# Sensor_Bar_2_0_signal_LED.net
KiCad netlist of a schematic drawn in Altium Designer
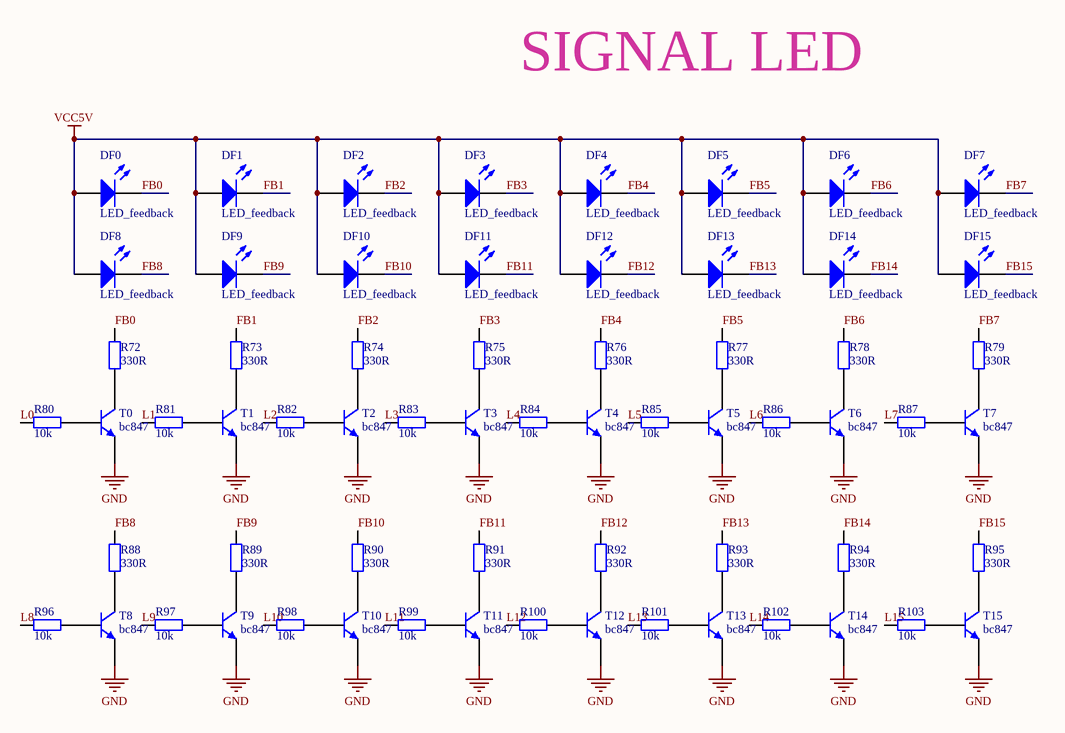
[diagram p0: Sensor Bar 2.0 signal LED.SchDoc]

(export (version "E")
  (design (tool "Eeschema 10.0.6"))
  (components
    (comp (ref "DF0")
      (value "LED_feedback")
      (footprint "SMD _LED")
      (description "Typical RED GaAs LED")
      (fields (field (name "PUBLISHER") "Altium Limited"))
      (libsource (lib "Robocon_BJT") (part "LED"))
    )
    (comp (ref "DF1")
      (value "LED_feedback")
      (footprint "SMD _LED")
      (description "Typical RED GaAs LED")
      (fields (field (name "PUBLISHER") "Altium Limited"))
      (libsource (lib "Robocon_BJT") (part "LED"))
    )
    (comp (ref "DF2")
      (value "LED_feedback")
      (footprint "SMD _LED")
      (description "Typical RED GaAs LED")
      (fields (field (name "PUBLISHER") "Altium Limited"))
      (libsource (lib "Robocon_BJT") (part "LED"))
    )
    (comp (ref "DF3")
      (value "LED_feedback")
      (footprint "SMD _LED")
      (description "Typical RED GaAs LED")
      (fields (field (name "PUBLISHER") "Altium Limited"))
      (libsource (lib "Robocon_BJT") (part "LED"))
    )
    (comp (ref "DF4")
      (value "LED_feedback")
      (footprint "SMD _LED")
      (description "Typical RED GaAs LED")
      (fields (field (name "PUBLISHER") "Altium Limited"))
      (libsource (lib "Robocon_BJT") (part "LED"))
    )
    (comp (ref "DF5")
      (value "LED_feedback")
      (footprint "SMD _LED")
      (description "Typical RED GaAs LED")
      (fields (field (name "PUBLISHER") "Altium Limited"))
      (libsource (lib "Robocon_BJT") (part "LED"))
    )
    (comp (ref "DF6")
      (value "LED_feedback")
      (footprint "SMD _LED")
      (description "Typical RED GaAs LED")
      (fields (field (name "PUBLISHER") "Altium Limited"))
      (libsource (lib "Robocon_BJT") (part "LED"))
    )
    (comp (ref "DF7")
      (value "LED_feedback")
      (footprint "SMD _LED")
      (description "Typical RED GaAs LED")
      (fields (field (name "PUBLISHER") "Altium Limited"))
      (libsource (lib "Robocon_BJT") (part "LED"))
    )
    (comp (ref "DF8")
      (value "LED_feedback")
      (footprint "SMD _LED")
      (description "Typical RED GaAs LED")
      (fields (field (name "PUBLISHER") "Altium Limited"))
      (libsource (lib "Robocon_BJT") (part "LED"))
    )
    (comp (ref "DF9")
      (value "LED_feedback")
      (footprint "SMD _LED")
      (description "Typical RED GaAs LED")
      (fields (field (name "PUBLISHER") "Altium Limited"))
      (libsource (lib "Robocon_BJT") (part "LED"))
    )
    (comp (ref "DF10")
      (value "LED_feedback")
      (footprint "SMD _LED")
      (description "Typical RED GaAs LED")
      (fields (field (name "PUBLISHER") "Altium Limited"))
      (libsource (lib "Robocon_BJT") (part "LED"))
    )
    (comp (ref "DF11")
      (value "LED_feedback")
      (footprint "SMD _LED")
      (description "Typical RED GaAs LED")
      (fields (field (name "PUBLISHER") "Altium Limited"))
      (libsource (lib "Robocon_BJT") (part "LED"))
    )
    (comp (ref "DF12")
      (value "LED_feedback")
      (footprint "SMD _LED")
      (description "Typical RED GaAs LED")
      (fields (field (name "PUBLISHER") "Altium Limited"))
      (libsource (lib "Robocon_BJT") (part "LED"))
    )
    (comp (ref "DF13")
      (value "LED_feedback")
      (footprint "SMD _LED")
      (description "Typical RED GaAs LED")
      (fields (field (name "PUBLISHER") "Altium Limited"))
      (libsource (lib "Robocon_BJT") (part "LED"))
    )
    (comp (ref "DF14")
      (value "LED_feedback")
      (footprint "SMD _LED")
      (description "Typical RED GaAs LED")
      (fields (field (name "PUBLISHER") "Altium Limited"))
      (libsource (lib "Robocon_BJT") (part "LED"))
    )
    (comp (ref "DF15")
      (value "LED_feedback")
      (footprint "SMD _LED")
      (description "Typical RED GaAs LED")
      (fields (field (name "PUBLISHER") "Altium Limited"))
      (libsource (lib "Robocon_BJT") (part "LED"))
    )
    (comp (ref "R72")
      (value "330R")
      (footprint "CR2012-0805")
      (description "Resistor")
      (fields (field (name "PUBLISHER") "Altium Limited"))
      (libsource (lib "Robocon_RCL") (part "Res2"))
    )
    (comp (ref "R73")
      (value "330R")
      (footprint "CR2012-0805")
      (description "Resistor")
      (fields (field (name "PUBLISHER") "Altium Limited"))
      (libsource (lib "Robocon_RCL") (part "Res2"))
    )
    (comp (ref "R74")
      (value "330R")
      (footprint "CR2012-0805")
      (description "Resistor")
      (fields (field (name "PUBLISHER") "Altium Limited"))
      (libsource (lib "Robocon_RCL") (part "Res2"))
    )
    (comp (ref "R75")
      (value "330R")
      (footprint "CR2012-0805")
      (description "Resistor")
      (fields (field (name "PUBLISHER") "Altium Limited"))
      (libsource (lib "Robocon_RCL") (part "Res2"))
    )
    (comp (ref "R76")
      (value "330R")
      (footprint "CR2012-0805")
      (description "Resistor")
      (fields (field (name "PUBLISHER") "Altium Limited"))
      (libsource (lib "Robocon_RCL") (part "Res2"))
    )
    (comp (ref "R77")
      (value "330R")
      (footprint "CR2012-0805")
      (description "Resistor")
      (fields (field (name "PUBLISHER") "Altium Limited"))
      (libsource (lib "Robocon_RCL") (part "Res2"))
    )
    (comp (ref "R78")
      (value "330R")
      (footprint "CR2012-0805")
      (description "Resistor")
      (fields (field (name "PUBLISHER") "Altium Limited"))
      (libsource (lib "Robocon_RCL") (part "Res2"))
    )
    (comp (ref "R79")
      (value "330R")
      (footprint "CR2012-0805")
      (description "Resistor")
      (fields (field (name "PUBLISHER") "Altium Limited"))
      (libsource (lib "Robocon_RCL") (part "Res2"))
    )
    (comp (ref "R80")
      (value "10k")
      (footprint "CR2012-0805")
      (description "Resistor")
      (fields (field (name "PUBLISHER") "Altium Limited"))
      (libsource (lib "") (part "Res2_1"))
    )
    (comp (ref "R81")
      (value "10k")
      (footprint "CR2012-0805")
      (description "Resistor")
      (fields (field (name "PUBLISHER") "Altium Limited"))
      (libsource (lib "") (part "Res2_1"))
    )
    (comp (ref "R82")
      (value "10k")
      (footprint "CR2012-0805")
      (description "Resistor")
      (fields (field (name "PUBLISHER") "Altium Limited"))
      (libsource (lib "") (part "Res2_1"))
    )
    (comp (ref "R83")
      (value "10k")
      (footprint "CR2012-0805")
      (description "Resistor")
      (fields (field (name "PUBLISHER") "Altium Limited"))
      (libsource (lib "") (part "Res2_1"))
    )
    (comp (ref "R84")
      (value "10k")
      (footprint "CR2012-0805")
      (description "Resistor")
      (fields (field (name "PUBLISHER") "Altium Limited"))
      (libsource (lib "") (part "Res2_1"))
    )
    (comp (ref "R85")
      (value "10k")
      (footprint "CR2012-0805")
      (description "Resistor")
      (fields (field (name "PUBLISHER") "Altium Limited"))
      (libsource (lib "") (part "Res2_1"))
    )
    (comp (ref "R86")
      (value "10k")
      (footprint "CR2012-0805")
      (description "Resistor")
      (fields (field (name "PUBLISHER") "Altium Limited"))
      (libsource (lib "") (part "Res2_1"))
    )
    (comp (ref "R87")
      (value "10k")
      (footprint "CR2012-0805")
      (description "Resistor")
      (fields (field (name "PUBLISHER") "Altium Limited"))
      (libsource (lib "") (part "Res2_1"))
    )
    (comp (ref "R88")
      (value "330R")
      (footprint "CR2012-0805")
      (description "Resistor")
      (fields (field (name "PUBLISHER") "Altium Limited"))
      (libsource (lib "Robocon_RCL") (part "Res2"))
    )
    (comp (ref "R89")
      (value "330R")
      (footprint "CR2012-0805")
      (description "Resistor")
      (fields (field (name "PUBLISHER") "Altium Limited"))
      (libsource (lib "Robocon_RCL") (part "Res2"))
    )
    (comp (ref "R90")
      (value "330R")
      (footprint "CR2012-0805")
      (description "Resistor")
      (fields (field (name "PUBLISHER") "Altium Limited"))
      (libsource (lib "Robocon_RCL") (part "Res2"))
    )
    (comp (ref "R91")
      (value "330R")
      (footprint "CR2012-0805")
      (description "Resistor")
      (fields (field (name "PUBLISHER") "Altium Limited"))
      (libsource (lib "Robocon_RCL") (part "Res2"))
    )
    (comp (ref "R92")
      (value "330R")
      (footprint "CR2012-0805")
      (description "Resistor")
      (fields (field (name "PUBLISHER") "Altium Limited"))
      (libsource (lib "Robocon_RCL") (part "Res2"))
    )
    (comp (ref "R93")
      (value "330R")
      (footprint "CR2012-0805")
      (description "Resistor")
      (fields (field (name "PUBLISHER") "Altium Limited"))
      (libsource (lib "Robocon_RCL") (part "Res2"))
    )
    (comp (ref "R94")
      (value "330R")
      (footprint "CR2012-0805")
      (description "Resistor")
      (fields (field (name "PUBLISHER") "Altium Limited"))
      (libsource (lib "Robocon_RCL") (part "Res2"))
    )
    (comp (ref "R95")
      (value "330R")
      (footprint "CR2012-0805")
      (description "Resistor")
      (fields (field (name "PUBLISHER") "Altium Limited"))
      (libsource (lib "Robocon_RCL") (part "Res2"))
    )
    (comp (ref "R96")
      (value "10k")
      (footprint "CR2012-0805")
      (description "Resistor")
      (fields (field (name "PUBLISHER") "Altium Limited"))
      (libsource (lib "") (part "Res2_1"))
    )
    (comp (ref "R97")
      (value "10k")
      (footprint "CR2012-0805")
      (description "Resistor")
      (fields (field (name "PUBLISHER") "Altium Limited"))
      (libsource (lib "") (part "Res2_1"))
    )
    (comp (ref "R98")
      (value "10k")
      (footprint "CR2012-0805")
      (description "Resistor")
      (fields (field (name "PUBLISHER") "Altium Limited"))
      (libsource (lib "") (part "Res2_1"))
    )
    (comp (ref "R99")
      (value "10k")
      (footprint "CR2012-0805")
      (description "Resistor")
      (fields (field (name "PUBLISHER") "Altium Limited"))
      (libsource (lib "") (part "Res2_1"))
    )
    (comp (ref "R100")
      (value "10k")
      (footprint "CR2012-0805")
      (description "Resistor")
      (fields (field (name "PUBLISHER") "Altium Limited"))
      (libsource (lib "") (part "Res2_1"))
    )
    (comp (ref "R101")
      (value "10k")
      (footprint "CR2012-0805")
      (description "Resistor")
      (fields (field (name "PUBLISHER") "Altium Limited"))
      (libsource (lib "") (part "Res2_1"))
    )
    (comp (ref "R102")
      (value "10k")
      (footprint "CR2012-0805")
      (description "Resistor")
      (fields (field (name "PUBLISHER") "Altium Limited"))
      (libsource (lib "") (part "Res2_1"))
    )
    (comp (ref "R103")
      (value "10k")
      (footprint "CR2012-0805")
      (description "Resistor")
      (fields (field (name "PUBLISHER") "Altium Limited"))
      (libsource (lib "") (part "Res2_1"))
    )
    (comp (ref "T0") (value "bc847") (footprint "npn") (libsource (lib "三极管") (part "npn")))
    (comp (ref "T1") (value "bc847") (footprint "npn") (libsource (lib "三极管") (part "npn")))
    (comp (ref "T2") (value "bc847") (footprint "npn") (libsource (lib "三极管") (part "npn")))
    (comp (ref "T3") (value "bc847") (footprint "npn") (libsource (lib "三极管") (part "npn")))
    (comp (ref "T4") (value "bc847") (footprint "npn") (libsource (lib "三极管") (part "npn")))
    (comp (ref "T5") (value "bc847") (footprint "npn") (libsource (lib "三极管") (part "npn")))
    (comp (ref "T6") (value "bc847") (footprint "npn") (libsource (lib "三极管") (part "npn")))
    (comp (ref "T7") (value "bc847") (footprint "npn") (libsource (lib "三极管") (part "npn")))
    (comp (ref "T8") (value "bc847") (footprint "npn") (libsource (lib "三极管") (part "npn")))
    (comp (ref "T9") (value "bc847") (footprint "npn") (libsource (lib "三极管") (part "npn")))
    (comp (ref "T10") (value "bc847") (footprint "npn") (libsource (lib "三极管") (part "npn")))
    (comp (ref "T11") (value "bc847") (footprint "npn") (libsource (lib "三极管") (part "npn")))
    (comp (ref "T12") (value "bc847") (footprint "npn") (libsource (lib "三极管") (part "npn")))
    (comp (ref "T13") (value "bc847") (footprint "npn") (libsource (lib "三极管") (part "npn")))
    (comp (ref "T14") (value "bc847") (footprint "npn") (libsource (lib "三极管") (part "npn")))
    (comp (ref "T15") (value "bc847") (footprint "npn") (libsource (lib "三极管") (part "npn")))
  )
  (nets
    (net (code "1") (name "/FB0") (class "Default")
      (node (ref "DF0") (pin "2") (pinfunction "K_2") (pintype "passive"))
      (node (ref "R72") (pin "2") (pinfunction "2_2") (pintype "passive"))
    )
    (net (code "2") (name "/FB1") (class "Default")
      (node (ref "DF1") (pin "2") (pinfunction "K_2") (pintype "passive"))
      (node (ref "R73") (pin "2") (pinfunction "2_2") (pintype "passive"))
    )
    (net (code "3") (name "/FB2") (class "Default")
      (node (ref "DF2") (pin "2") (pinfunction "K_2") (pintype "passive"))
      (node (ref "R74") (pin "2") (pinfunction "2_2") (pintype "passive"))
    )
    (net (code "4") (name "/FB3") (class "Default")
      (node (ref "DF3") (pin "2") (pinfunction "K_2") (pintype "passive"))
      (node (ref "R75") (pin "2") (pinfunction "2_2") (pintype "passive"))
    )
    (net (code "5") (name "/FB4") (class "Default")
      (node (ref "DF4") (pin "2") (pinfunction "K_2") (pintype "passive"))
      (node (ref "R76") (pin "2") (pinfunction "2_2") (pintype "passive"))
    )
    (net (code "6") (name "/FB5") (class "Default")
      (node (ref "DF5") (pin "2") (pinfunction "K_2") (pintype "passive"))
      (node (ref "R77") (pin "2") (pinfunction "2_2") (pintype "passive"))
    )
    (net (code "7") (name "/FB6") (class "Default")
      (node (ref "DF6") (pin "2") (pinfunction "K_2") (pintype "passive"))
      (node (ref "R78") (pin "2") (pinfunction "2_2") (pintype "passive"))
    )
    (net (code "8") (name "/FB7") (class "Default")
      (node (ref "DF7") (pin "2") (pinfunction "K_2") (pintype "passive"))
      (node (ref "R79") (pin "2") (pinfunction "2_2") (pintype "passive"))
    )
    (net (code "9") (name "/FB8") (class "Default")
      (node (ref "DF8") (pin "2") (pinfunction "K_2") (pintype "passive"))
      (node (ref "R88") (pin "2") (pinfunction "2_2") (pintype "passive"))
    )
    (net (code "10") (name "/FB9") (class "Default")
      (node (ref "DF9") (pin "2") (pinfunction "K_2") (pintype "passive"))
      (node (ref "R89") (pin "2") (pinfunction "2_2") (pintype "passive"))
    )
    (net (code "11") (name "/FB10") (class "Default")
      (node (ref "DF10") (pin "2") (pinfunction "K_2") (pintype "passive"))
      (node (ref "R90") (pin "2") (pinfunction "2_2") (pintype "passive"))
    )
    (net (code "12") (name "/FB11") (class "Default")
      (node (ref "DF11") (pin "2") (pinfunction "K_2") (pintype "passive"))
      (node (ref "R91") (pin "2") (pinfunction "2_2") (pintype "passive"))
    )
    (net (code "13") (name "/FB12") (class "Default")
      (node (ref "DF12") (pin "2") (pinfunction "K_2") (pintype "passive"))
      (node (ref "R92") (pin "2") (pinfunction "2_2") (pintype "passive"))
    )
    (net (code "14") (name "/FB13") (class "Default")
      (node (ref "DF13") (pin "2") (pinfunction "K_2") (pintype "passive"))
      (node (ref "R93") (pin "2") (pinfunction "2_2") (pintype "passive"))
    )
    (net (code "15") (name "/FB14") (class "Default")
      (node (ref "DF14") (pin "2") (pinfunction "K_2") (pintype "passive"))
      (node (ref "R94") (pin "2") (pinfunction "2_2") (pintype "passive"))
    )
    (net (code "16") (name "/FB15") (class "Default")
      (node (ref "DF15") (pin "2") (pinfunction "K_2") (pintype "passive"))
      (node (ref "R95") (pin "2") (pinfunction "2_2") (pintype "passive"))
    )
    (net (code "17") (name "/L0") (class "Default")
      (node (ref "R80") (pin "2") (pinfunction "2_2") (pintype "passive"))
    )
    (net (code "18") (name "/L1") (class "Default")
      (node (ref "R81") (pin "2") (pinfunction "2_2") (pintype "passive"))
    )
    (net (code "19") (name "/L2") (class "Default")
      (node (ref "R82") (pin "2") (pinfunction "2_2") (pintype "passive"))
    )
    (net (code "20") (name "/L3") (class "Default")
      (node (ref "R83") (pin "2") (pinfunction "2_2") (pintype "passive"))
    )
    (net (code "21") (name "/L4") (class "Default")
      (node (ref "R84") (pin "2") (pinfunction "2_2") (pintype "passive"))
    )
    (net (code "22") (name "/L5") (class "Default")
      (node (ref "R85") (pin "2") (pinfunction "2_2") (pintype "passive"))
    )
    (net (code "23") (name "/L6") (class "Default")
      (node (ref "R86") (pin "2") (pinfunction "2_2") (pintype "passive"))
    )
    (net (code "24") (name "/L7") (class "Default")
      (node (ref "R87") (pin "2") (pinfunction "2_2") (pintype "passive"))
    )
    (net (code "25") (name "/L8") (class "Default")
      (node (ref "R96") (pin "2") (pinfunction "2_2") (pintype "passive"))
    )
    (net (code "26") (name "/L9") (class "Default")
      (node (ref "R97") (pin "2") (pinfunction "2_2") (pintype "passive"))
    )
    (net (code "27") (name "/L10") (class "Default")
      (node (ref "R98") (pin "2") (pinfunction "2_2") (pintype "passive"))
    )
    (net (code "28") (name "/L11") (class "Default")
      (node (ref "R99") (pin "2") (pinfunction "2_2") (pintype "passive"))
    )
    (net (code "29") (name "/L12") (class "Default")
      (node (ref "R100") (pin "2") (pinfunction "2_2") (pintype "passive"))
    )
    (net (code "30") (name "/L13") (class "Default")
      (node (ref "R101") (pin "2") (pinfunction "2_2") (pintype "passive"))
    )
    (net (code "31") (name "/L14") (class "Default")
      (node (ref "R102") (pin "2") (pinfunction "2_2") (pintype "passive"))
    )
    (net (code "32") (name "/L15") (class "Default")
      (node (ref "R103") (pin "2") (pinfunction "2_2") (pintype "passive"))
    )
    (net (code "33") (name "GND") (class "Default")
      (node (ref "T0") (pin "2") (pinfunction "E_2") (pintype "passive"))
      (node (ref "T1") (pin "2") (pinfunction "E_2") (pintype "passive"))
      (node (ref "T10") (pin "2") (pinfunction "E_2") (pintype "passive"))
      (node (ref "T11") (pin "2") (pinfunction "E_2") (pintype "passive"))
      (node (ref "T12") (pin "2") (pinfunction "E_2") (pintype "passive"))
      (node (ref "T13") (pin "2") (pinfunction "E_2") (pintype "passive"))
      (node (ref "T14") (pin "2") (pinfunction "E_2") (pintype "passive"))
      (node (ref "T15") (pin "2") (pinfunction "E_2") (pintype "passive"))
      (node (ref "T2") (pin "2") (pinfunction "E_2") (pintype "passive"))
      (node (ref "T3") (pin "2") (pinfunction "E_2") (pintype "passive"))
      (node (ref "T4") (pin "2") (pinfunction "E_2") (pintype "passive"))
      (node (ref "T5") (pin "2") (pinfunction "E_2") (pintype "passive"))
      (node (ref "T6") (pin "2") (pinfunction "E_2") (pintype "passive"))
      (node (ref "T7") (pin "2") (pinfunction "E_2") (pintype "passive"))
      (node (ref "T8") (pin "2") (pinfunction "E_2") (pintype "passive"))
      (node (ref "T9") (pin "2") (pinfunction "E_2") (pintype "passive"))
    )
    (net (code "34") (name "Net-(T0-B)") (class "Default")
      (node (ref "R80") (pin "1") (pinfunction "1_1") (pintype "passive"))
      (node (ref "T0") (pin "1") (pinfunction "B_1") (pintype "passive"))
    )
    (net (code "35") (name "Net-(T0-C)") (class "Default")
      (node (ref "R72") (pin "1") (pinfunction "1_1") (pintype "passive"))
      (node (ref "T0") (pin "3") (pinfunction "C_3") (pintype "passive"))
    )
    (net (code "36") (name "Net-(T1-B)") (class "Default")
      (node (ref "R81") (pin "1") (pinfunction "1_1") (pintype "passive"))
      (node (ref "T1") (pin "1") (pinfunction "B_1") (pintype "passive"))
    )
    (net (code "37") (name "Net-(T1-C)") (class "Default")
      (node (ref "R73") (pin "1") (pinfunction "1_1") (pintype "passive"))
      (node (ref "T1") (pin "3") (pinfunction "C_3") (pintype "passive"))
    )
    (net (code "38") (name "Net-(T2-B)") (class "Default")
      (node (ref "R82") (pin "1") (pinfunction "1_1") (pintype "passive"))
      (node (ref "T2") (pin "1") (pinfunction "B_1") (pintype "passive"))
    )
    (net (code "39") (name "Net-(T2-C)") (class "Default")
      (node (ref "R74") (pin "1") (pinfunction "1_1") (pintype "passive"))
      (node (ref "T2") (pin "3") (pinfunction "C_3") (pintype "passive"))
    )
    (net (code "40") (name "Net-(T3-B)") (class "Default")
      (node (ref "R83") (pin "1") (pinfunction "1_1") (pintype "passive"))
      (node (ref "T3") (pin "1") (pinfunction "B_1") (pintype "passive"))
    )
    (net (code "41") (name "Net-(T3-C)") (class "Default")
      (node (ref "R75") (pin "1") (pinfunction "1_1") (pintype "passive"))
      (node (ref "T3") (pin "3") (pinfunction "C_3") (pintype "passive"))
    )
    (net (code "42") (name "Net-(T4-B)") (class "Default")
      (node (ref "R84") (pin "1") (pinfunction "1_1") (pintype "passive"))
      (node (ref "T4") (pin "1") (pinfunction "B_1") (pintype "passive"))
    )
    (net (code "43") (name "Net-(T4-C)") (class "Default")
      (node (ref "R76") (pin "1") (pinfunction "1_1") (pintype "passive"))
      (node (ref "T4") (pin "3") (pinfunction "C_3") (pintype "passive"))
    )
    (net (code "44") (name "Net-(T5-B)") (class "Default")
      (node (ref "R85") (pin "1") (pinfunction "1_1") (pintype "passive"))
      (node (ref "T5") (pin "1") (pinfunction "B_1") (pintype "passive"))
    )
    (net (code "45") (name "Net-(T5-C)") (class "Default")
      (node (ref "R77") (pin "1") (pinfunction "1_1") (pintype "passive"))
      (node (ref "T5") (pin "3") (pinfunction "C_3") (pintype "passive"))
    )
    (net (code "46") (name "Net-(T6-B)") (class "Default")
      (node (ref "R86") (pin "1") (pinfunction "1_1") (pintype "passive"))
      (node (ref "T6") (pin "1") (pinfunction "B_1") (pintype "passive"))
    )
    (net (code "47") (name "Net-(T6-C)") (class "Default")
      (node (ref "R78") (pin "1") (pinfunction "1_1") (pintype "passive"))
      (node (ref "T6") (pin "3") (pinfunction "C_3") (pintype "passive"))
    )
    (net (code "48") (name "Net-(T7-B)") (class "Default")
      (node (ref "R87") (pin "1") (pinfunction "1_1") (pintype "passive"))
      (node (ref "T7") (pin "1") (pinfunction "B_1") (pintype "passive"))
    )
    (net (code "49") (name "Net-(T7-C)") (class "Default")
      (node (ref "R79") (pin "1") (pinfunction "1_1") (pintype "passive"))
      (node (ref "T7") (pin "3") (pinfunction "C_3") (pintype "passive"))
    )
    (net (code "50") (name "Net-(T8-B)") (class "Default")
      (node (ref "R96") (pin "1") (pinfunction "1_1") (pintype "passive"))
      (node (ref "T8") (pin "1") (pinfunction "B_1") (pintype "passive"))
    )
    (net (code "51") (name "Net-(T8-C)") (class "Default")
      (node (ref "R88") (pin "1") (pinfunction "1_1") (pintype "passive"))
      (node (ref "T8") (pin "3") (pinfunction "C_3") (pintype "passive"))
    )
    (net (code "52") (name "Net-(T9-B)") (class "Default")
      (node (ref "R97") (pin "1") (pinfunction "1_1") (pintype "passive"))
      (node (ref "T9") (pin "1") (pinfunction "B_1") (pintype "passive"))
    )
    (net (code "53") (name "Net-(T9-C)") (class "Default")
      (node (ref "R89") (pin "1") (pinfunction "1_1") (pintype "passive"))
      (node (ref "T9") (pin "3") (pinfunction "C_3") (pintype "passive"))
    )
    (net (code "54") (name "Net-(T10-B)") (class "Default")
      (node (ref "R98") (pin "1") (pinfunction "1_1") (pintype "passive"))
      (node (ref "T10") (pin "1") (pinfunction "B_1") (pintype "passive"))
    )
    (net (code "55") (name "Net-(T10-C)") (class "Default")
      (node (ref "R90") (pin "1") (pinfunction "1_1") (pintype "passive"))
      (node (ref "T10") (pin "3") (pinfunction "C_3") (pintype "passive"))
    )
    (net (code "56") (name "Net-(T11-B)") (class "Default")
      (node (ref "R99") (pin "1") (pinfunction "1_1") (pintype "passive"))
      (node (ref "T11") (pin "1") (pinfunction "B_1") (pintype "passive"))
    )
    (net (code "57") (name "Net-(T11-C)") (class "Default")
      (node (ref "R91") (pin "1") (pinfunction "1_1") (pintype "passive"))
      (node (ref "T11") (pin "3") (pinfunction "C_3") (pintype "passive"))
    )
    (net (code "58") (name "Net-(T12-B)") (class "Default")
      (node (ref "R100") (pin "1") (pinfunction "1_1") (pintype "passive"))
      (node (ref "T12") (pin "1") (pinfunction "B_1") (pintype "passive"))
    )
    (net (code "59") (name "Net-(T12-C)") (class "Default")
      (node (ref "R92") (pin "1") (pinfunction "1_1") (pintype "passive"))
      (node (ref "T12") (pin "3") (pinfunction "C_3") (pintype "passive"))
    )
    (net (code "60") (name "Net-(T13-B)") (class "Default")
      (node (ref "R101") (pin "1") (pinfunction "1_1") (pintype "passive"))
      (node (ref "T13") (pin "1") (pinfunction "B_1") (pintype "passive"))
    )
    (net (code "61") (name "Net-(T13-C)") (class "Default")
      (node (ref "R93") (pin "1") (pinfunction "1_1") (pintype "passive"))
      (node (ref "T13") (pin "3") (pinfunction "C_3") (pintype "passive"))
    )
    (net (code "62") (name "Net-(T14-B)") (class "Default")
      (node (ref "R102") (pin "1") (pinfunction "1_1") (pintype "passive"))
      (node (ref "T14") (pin "1") (pinfunction "B_1") (pintype "passive"))
    )
    (net (code "63") (name "Net-(T14-C)") (class "Default")
      (node (ref "R94") (pin "1") (pinfunction "1_1") (pintype "passive"))
      (node (ref "T14") (pin "3") (pinfunction "C_3") (pintype "passive"))
    )
    (net (code "64") (name "Net-(T15-B)") (class "Default")
      (node (ref "R103") (pin "1") (pinfunction "1_1") (pintype "passive"))
      (node (ref "T15") (pin "1") (pinfunction "B_1") (pintype "passive"))
    )
    (net (code "65") (name "Net-(T15-C)") (class "Default")
      (node (ref "R95") (pin "1") (pinfunction "1_1") (pintype "passive"))
      (node (ref "T15") (pin "3") (pinfunction "C_3") (pintype "passive"))
    )
    (net (code "66") (name "VCC5V") (class "Default")
      (node (ref "DF0") (pin "1") (pinfunction "A_1") (pintype "passive"))
      (node (ref "DF1") (pin "1") (pinfunction "A_1") (pintype "passive"))
      (node (ref "DF10") (pin "1") (pinfunction "A_1") (pintype "passive"))
      (node (ref "DF11") (pin "1") (pinfunction "A_1") (pintype "passive"))
      (node (ref "DF12") (pin "1") (pinfunction "A_1") (pintype "passive"))
      (node (ref "DF13") (pin "1") (pinfunction "A_1") (pintype "passive"))
      (node (ref "DF14") (pin "1") (pinfunction "A_1") (pintype "passive"))
      (node (ref "DF15") (pin "1") (pinfunction "A_1") (pintype "passive"))
      (node (ref "DF2") (pin "1") (pinfunction "A_1") (pintype "passive"))
      (node (ref "DF3") (pin "1") (pinfunction "A_1") (pintype "passive"))
      (node (ref "DF4") (pin "1") (pinfunction "A_1") (pintype "passive"))
      (node (ref "DF5") (pin "1") (pinfunction "A_1") (pintype "passive"))
      (node (ref "DF6") (pin "1") (pinfunction "A_1") (pintype "passive"))
      (node (ref "DF7") (pin "1") (pinfunction "A_1") (pintype "passive"))
      (node (ref "DF8") (pin "1") (pinfunction "A_1") (pintype "passive"))
      (node (ref "DF9") (pin "1") (pinfunction "A_1") (pintype "passive"))
    )
  )
)
